# MCU_64.net
KiCad netlist of a schematic drawn in Altium Designer
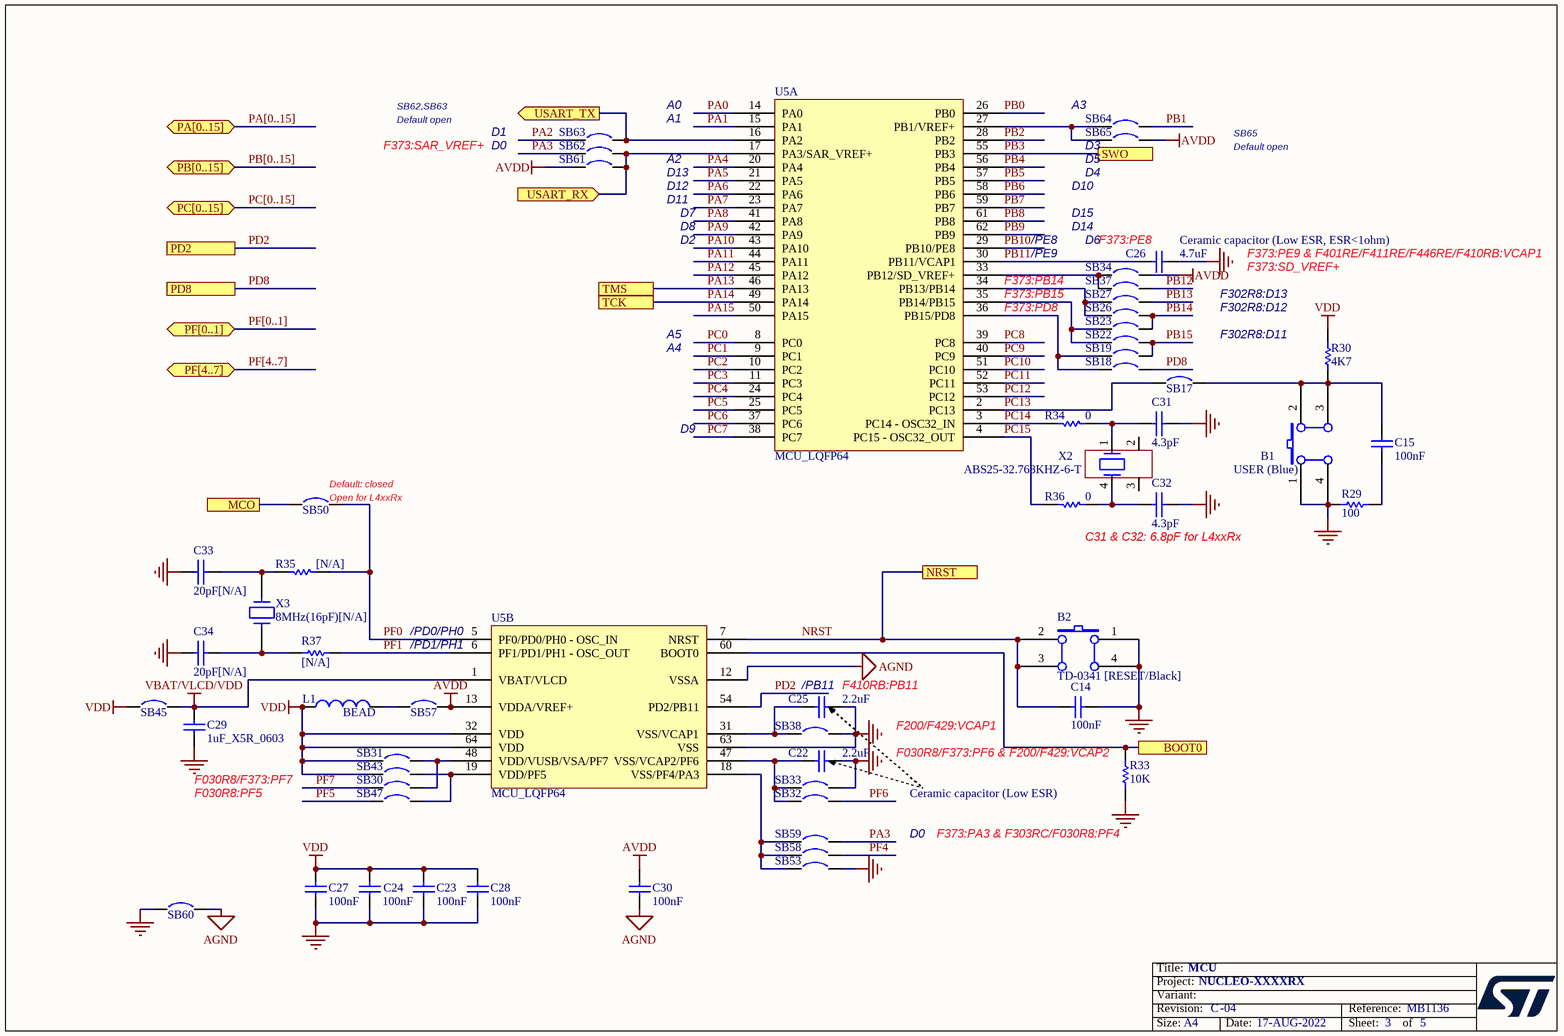
[diagram p0: MCU_64.SchDoc]

(export (version "E")
  (design (tool "Eeschema 10.0.6"))
  (components
    (comp (ref "B1")
      (value "USER (Blue)")
      (footprint "PB10")
      (description "SE PUSHBUTTON")
      (libsource (lib "Documents") (part "SW PUSHBUTTON"))
    )
    (comp (ref "B2")
      (value "TD-0341 [RESET/Black]")
      (footprint "PB10")
      (description "SE PUSHBUTTON")
      (libsource (lib "Documents") (part "SW PUSHBUTTON"))
    )
    (comp (ref "C14")
      (value "100nF")
      (footprint "0603C")
      (description "Capacitor")
      (fields (field (name "PUBLISHER") "Altium Limited"))
      (libsource (lib "Miscellaneous Devices") (part "CAP"))
    )
    (comp (ref "C15")
      (value "100nF")
      (footprint "0603C")
      (description "Capacitor")
      (fields (field (name "PUBLISHER") "Altium Limited"))
      (libsource (lib "Miscellaneous Devices") (part "CAP"))
    )
    (comp (ref "C22")
      (value "2.2uF")
      (footprint "TAN-A")
      (description "Capacitor,2.2uF,16V, X7R,10%,0805,YAGEO")
      (libsource (lib "MCD_TOOLS") (part "Cap_2.2uF_X7R_10%_0805"))
    )
    (comp (ref "C23")
      (value "100nF")
      (footprint "0603C")
      (description "Capacitor")
      (fields (field (name "PUBLISHER") "Altium Limited"))
      (libsource (lib "Miscellaneous Devices") (part "Cap"))
    )
    (comp (ref "C24")
      (value "100nF")
      (footprint "0603C")
      (description "Capacitor")
      (fields (field (name "PUBLISHER") "Altium Limited"))
      (libsource (lib "Miscellaneous Devices") (part "Cap"))
    )
    (comp (ref "C25")
      (value "2.2uF")
      (footprint "TAN-A")
      (description "Capacitor,2.2uF,16V, X7R,10%,0805,YAGEO")
      (libsource (lib "MCD_TOOLS") (part "Cap_2.2uF_X7R_10%_0805"))
    )
    (comp (ref "C26")
      (value "4.7uF")
      (footprint "TAN-A")
      (description "Capacitor,4.7uF,25V, X7R,10%,1206,YAGEO")
      (libsource (lib "MCD_TOOLS") (part "Cap_2.2uF_X7R_10%_0805"))
    )
    (comp (ref "C27")
      (value "100nF")
      (footprint "0603C")
      (description "Capacitor")
      (fields (field (name "PUBLISHER") "Altium Limited"))
      (libsource (lib "Miscellaneous Devices") (part "Cap"))
    )
    (comp (ref "C28")
      (value "100nF")
      (footprint "0603C")
      (description "Capacitor")
      (fields (field (name "PUBLISHER") "Altium Limited"))
      (libsource (lib "Miscellaneous Devices") (part "Cap"))
    )
    (comp (ref "C29")
      (value "1uF_X5R_0603")
      (footprint "0603C")
      (description "0603  X5R 1µF")
      (fields (field (name "TOLERANCE") "10%"))
      (libsource (lib "MB963_1") (part "CAP SMD 0603  X5R 1µF 25V 10%"))
    )
    (comp (ref "C30")
      (value "100nF")
      (footprint "0603C")
      (description "Capacitor")
      (fields (field (name "PUBLISHER") "Altium Limited"))
      (libsource (lib "Miscellaneous Devices") (part "Cap"))
    )
    (comp (ref "C31")
      (value "4.3pF")
      (footprint "0603C")
      (description "Capacitor")
      (libsource (lib "*") (part "CAP"))
    )
    (comp (ref "C32")
      (value "4.3pF")
      (footprint "0603C")
      (description "Capacitor")
      (libsource (lib "*") (part "CAP"))
    )
    (comp (ref "C33")
      (value "20pF[N/A]")
      (footprint "0603C")
      (description "Capacitor")
      (libsource (lib "") (part "CAP_1"))
    )
    (comp (ref "C34")
      (value "20pF[N/A]")
      (footprint "0603C")
      (description "Capacitor")
      (libsource (lib "") (part "CAP_1"))
    )
    (comp (ref "L1")
      (value "BEAD")
      (footprint "0603L")
      (description "Inductor")
      (fields (field (name "PUBLISHER") "Altium Limited"))
      (libsource (lib "Miscellaneous Devices") (part "Inductor"))
    )
    (comp (ref "R29")
      (value "100")
      (footprint "0603R")
      (description "Resistor")
      (fields (field (name "PUBLISHER") "Altium Limited"))
      (libsource (lib "Miscellaneous Devices") (part "Res1"))
    )
    (comp (ref "R30")
      (value "4K7")
      (footprint "0603R")
      (description "Resistor")
      (fields (field (name "PUBLISHER") "Altium Limited"))
      (libsource (lib "Miscellaneous Devices") (part "res1"))
    )
    (comp (ref "R33")
      (value "10K")
      (footprint "0603R")
      (description "Resistor")
      (fields (field (name "PUBLISHER") "Altium Limited"))
      (libsource (lib "Miscellaneous Devices") (part "res1"))
    )
    (comp (ref "R34")
      (value "0")
      (footprint "0603R")
      (description "Resistor")
      (fields (field (name "PUBLISHER") "Altium Limited"))
      (libsource (lib "") (part "Res1_1"))
    )
    (comp (ref "R35")
      (value "[N/A]")
      (footprint "0603R")
      (description "Resistor")
      (fields (field (name "PUBLISHER") "Altium Limited"))
      (libsource (lib "") (part "Res1_1"))
    )
    (comp (ref "R36")
      (value "0")
      (footprint "0603R")
      (description "Resistor")
      (fields (field (name "PUBLISHER") "Altium Limited"))
      (libsource (lib "") (part "Res1_1"))
    )
    (comp (ref "R37")
      (value "[N/A]")
      (footprint "0603R")
      (description "Resistor")
      (fields (field (name "PUBLISHER") "Altium Limited"))
      (libsource (lib "Miscellaneous Devices") (part "Res1"))
    )
    (comp (ref "SB17")
      (value "Circuit Breaker")
      (footprint "JP2_SMD")
      (fields (field (name "PUBLISHER") "Altium Limited"))
      (libsource (lib "MCD_TOOLS") (part "Circuit Breaker"))
    )
    (comp (ref "SB18")
      (value "Circuit Breaker")
      (footprint "JP2_SMD")
      (fields (field (name "PUBLISHER") "Altium Limited"))
      (libsource (lib "MCD_TOOLS") (part "Circuit Breaker"))
    )
    (comp (ref "SB19")
      (value "Circuit Breaker")
      (footprint "JP2_SMD")
      (fields (field (name "PUBLISHER") "Altium Limited"))
      (libsource (lib "MCD_TOOLS") (part "Circuit Breaker"))
    )
    (comp (ref "SB22")
      (value "Circuit Breaker")
      (footprint "JP2_SMD")
      (fields (field (name "PUBLISHER") "Altium Limited"))
      (libsource (lib "MCD_TOOLS") (part "Circuit Breaker"))
    )
    (comp (ref "SB23")
      (value "Circuit Breaker")
      (footprint "JP2_SMD")
      (fields (field (name "PUBLISHER") "Altium Limited"))
      (libsource (lib "MCD_TOOLS") (part "Circuit Breaker"))
    )
    (comp (ref "SB26")
      (value "Circuit Breaker")
      (footprint "JP2_SMD")
      (fields (field (name "PUBLISHER") "Altium Limited"))
      (libsource (lib "MCD_TOOLS") (part "Circuit Breaker"))
    )
    (comp (ref "SB27")
      (value "Circuit Breaker")
      (footprint "JP2_SMD")
      (fields (field (name "PUBLISHER") "Altium Limited"))
      (libsource (lib "MCD_TOOLS") (part "Circuit Breaker"))
    )
    (comp (ref "SB30")
      (value "Circuit Breaker")
      (footprint "JP2_SMD")
      (fields (field (name "PUBLISHER") "Altium Limited"))
      (libsource (lib "MCD_TOOLS") (part "Circuit Breaker"))
    )
    (comp (ref "SB31")
      (value "Circuit Breaker")
      (footprint "JP2_SMD")
      (fields (field (name "PUBLISHER") "Altium Limited"))
      (libsource (lib "MCD_TOOLS") (part "Circuit Breaker"))
    )
    (comp (ref "SB32")
      (value "Circuit Breaker")
      (footprint "JP2_SMD")
      (fields (field (name "PUBLISHER") "Altium Limited"))
      (libsource (lib "MCD_TOOLS") (part "Circuit Breaker"))
    )
    (comp (ref "SB33")
      (value "Circuit Breaker")
      (footprint "JP2_SMD")
      (fields (field (name "PUBLISHER") "Altium Limited"))
      (libsource (lib "MCD_TOOLS") (part "Circuit Breaker"))
    )
    (comp (ref "SB34")
      (value "Circuit Breaker")
      (footprint "JP2_SMD")
      (fields (field (name "PUBLISHER") "Altium Limited"))
      (libsource (lib "MCD_TOOLS") (part "Circuit Breaker"))
    )
    (comp (ref "SB37")
      (value "Circuit Breaker")
      (footprint "JP2_SMD")
      (fields (field (name "PUBLISHER") "Altium Limited"))
      (libsource (lib "MCD_TOOLS") (part "Circuit Breaker"))
    )
    (comp (ref "SB38")
      (value "Circuit Breaker")
      (footprint "JP2_SMD")
      (fields (field (name "PUBLISHER") "Altium Limited"))
      (libsource (lib "MCD_TOOLS") (part "Circuit Breaker"))
    )
    (comp (ref "SB43")
      (value "Circuit Breaker")
      (footprint "JP2_SMD")
      (fields (field (name "PUBLISHER") "Altium Limited"))
      (libsource (lib "MCD_TOOLS") (part "Circuit Breaker"))
    )
    (comp (ref "SB45")
      (value "Circuit Breaker")
      (footprint "JP2_SMD")
      (fields (field (name "PUBLISHER") "Altium Limited"))
      (libsource (lib "MCD_TOOLS") (part "Circuit Breaker"))
    )
    (comp (ref "SB47")
      (value "Circuit Breaker")
      (footprint "JP2_SMD")
      (fields (field (name "PUBLISHER") "Altium Limited"))
      (libsource (lib "MCD_TOOLS") (part "Circuit Breaker"))
    )
    (comp (ref "SB50")
      (value "Circuit Breaker")
      (footprint "JP2_SMD")
      (fields (field (name "PUBLISHER") "Altium Limited"))
      (libsource (lib "MCD_TOOLS") (part "Circuit Breaker"))
    )
    (comp (ref "SB53")
      (value "Circuit Breaker")
      (footprint "JP2_SMD")
      (fields (field (name "PUBLISHER") "Altium Limited"))
      (libsource (lib "MCD_TOOLS") (part "Circuit Breaker"))
    )
    (comp (ref "SB57")
      (value "Circuit Breaker")
      (footprint "JP2_SMD")
      (fields (field (name "PUBLISHER") "Altium Limited"))
      (libsource (lib "MCD_TOOLS") (part "Circuit Breaker"))
    )
    (comp (ref "SB58")
      (value "Circuit Breaker")
      (footprint "JP2_SMD")
      (fields (field (name "PUBLISHER") "Altium Limited"))
      (libsource (lib "MCD_TOOLS") (part "Circuit Breaker"))
    )
    (comp (ref "SB59")
      (value "Circuit Breaker")
      (footprint "JP2_SMD")
      (fields (field (name "PUBLISHER") "Altium Limited"))
      (libsource (lib "MCD_TOOLS") (part "Circuit Breaker"))
    )
    (comp (ref "SB60")
      (value "Circuit Breaker")
      (footprint "JP2_SMD")
      (fields (field (name "PUBLISHER") "Altium Limited"))
      (libsource (lib "MCD_TOOLS") (part "Circuit Breaker"))
    )
    (comp (ref "SB61")
      (value "Circuit Breaker")
      (footprint "JP2_SMD")
      (fields (field (name "PUBLISHER") "Altium Limited"))
      (libsource (lib "MCD_TOOLS") (part "Circuit Breaker"))
    )
    (comp (ref "SB62")
      (value "Circuit Breaker")
      (footprint "JP2_SMD")
      (fields (field (name "PUBLISHER") "Altium Limited"))
      (libsource (lib "MCD_TOOLS") (part "Circuit Breaker"))
    )
    (comp (ref "SB63")
      (value "Circuit Breaker")
      (footprint "JP2_SMD")
      (fields (field (name "PUBLISHER") "Altium Limited"))
      (libsource (lib "MCD_TOOLS") (part "Circuit Breaker"))
    )
    (comp (ref "SB64")
      (value "Circuit Breaker")
      (footprint "JP2_SMD")
      (fields (field (name "PUBLISHER") "Altium Limited"))
      (libsource (lib "MCD_TOOLS") (part "Circuit Breaker"))
    )
    (comp (ref "SB65")
      (value "Circuit Breaker")
      (footprint "JP2_SMD")
      (fields (field (name "PUBLISHER") "Altium Limited"))
      (libsource (lib "MCD_TOOLS") (part "Circuit Breaker"))
    )
    (comp (ref "U5") (value "MCU_LQFP64") (footprint "LQFP64") (libsource (lib "MB1136") (part "MCU_LQFP64")))
    (comp (ref "X2")
      (value "ABS25-32.768KHZ-6-T")
      (footprint "XTAL_4SM_8X3R8")
      (libsource (lib "*") (part "MC306"))
    )
    (comp (ref "X3")
      (value "8MHz(16pF)[N/A]")
      (footprint "XTAL1")
      (description "Crystal")
      (libsource (lib "*") (part "CRYSTAL"))
    )
  )
  (nets
    (net (code "1") (name "/BOOT0") (class "Default")
      (node (ref "R33") (pin "1") (pinfunction "1_1") (pintype "passive"))
      (node (ref "U5") (pin "60") (pinfunction "BOOT0_60") (pintype "passive"))
    )
    (net (code "2") (name "/MCO") (class "Default")
      (node (ref "SB50") (pin "1") (pinfunction "1_1") (pintype "passive"))
    )
    (net (code "3") (name "/NRST") (class "Default")
      (node (ref "B2") (pin "2") (pinfunction "B0_2") (pintype "passive"))
      (node (ref "B2") (pin "3") (pinfunction "B1_3") (pintype "passive"))
      (node (ref "C14") (pin "2") (pinfunction "2_2") (pintype "passive"))
      (node (ref "U5") (pin "7") (pinfunction "NRST_7") (pintype "passive"))
    )
    (net (code "4") (name "/PA0") (class "Default")
      (node (ref "U5") (pin "14") (pinfunction "PA0_14") (pintype "passive"))
    )
    (net (code "5") (name "/PA1") (class "Default")
      (node (ref "U5") (pin "15") (pinfunction "PA1_15") (pintype "passive"))
    )
    (net (code "6") (name "/PA2") (class "Default")
      (node (ref "SB63") (pin "1") (pinfunction "1_1") (pintype "passive"))
    )
    (net (code "7") (name "/PA3") (class "Default")
      (node (ref "SB59") (pin "2") (pinfunction "2_2") (pintype "passive"))
      (node (ref "SB62") (pin "1") (pinfunction "1_1") (pintype "passive"))
    )
    (net (code "8") (name "/PA4") (class "Default")
      (node (ref "U5") (pin "20") (pinfunction "PA4_20") (pintype "passive"))
    )
    (net (code "9") (name "/PA5") (class "Default")
      (node (ref "U5") (pin "21") (pinfunction "PA5_21") (pintype "passive"))
    )
    (net (code "10") (name "/PA6") (class "Default")
      (node (ref "U5") (pin "22") (pinfunction "PA6_22") (pintype "passive"))
    )
    (net (code "11") (name "/PA7") (class "Default")
      (node (ref "U5") (pin "23") (pinfunction "PA7_23") (pintype "passive"))
    )
    (net (code "12") (name "/PA8") (class "Default")
      (node (ref "U5") (pin "41") (pinfunction "PA8_41") (pintype "passive"))
    )
    (net (code "13") (name "/PA9") (class "Default")
      (node (ref "U5") (pin "42") (pinfunction "PA9_42") (pintype "passive"))
    )
    (net (code "14") (name "/PA10") (class "Default")
      (node (ref "U5") (pin "43") (pinfunction "PA10_43") (pintype "passive"))
    )
    (net (code "15") (name "/PA11") (class "Default")
      (node (ref "U5") (pin "44") (pinfunction "PA11_44") (pintype "passive"))
    )
    (net (code "16") (name "/PA12") (class "Default")
      (node (ref "U5") (pin "45") (pinfunction "PA12_45") (pintype "passive"))
    )
    (net (code "17") (name "/PA13") (class "Default")
      (node (ref "U5") (pin "46") (pinfunction "PA13_46") (pintype "passive"))
    )
    (net (code "18") (name "/PA14") (class "Default")
      (node (ref "U5") (pin "49") (pinfunction "PA14_49") (pintype "passive"))
    )
    (net (code "19") (name "/PA15") (class "Default")
      (node (ref "U5") (pin "50") (pinfunction "PA15_50") (pintype "passive"))
    )
    (net (code "21") (name "/PB0") (class "Default")
      (node (ref "U5") (pin "26") (pinfunction "PB0_26") (pintype "passive"))
    )
    (net (code "22") (name "/PB1") (class "Default")
      (node (ref "SB64") (pin "2") (pinfunction "2_2") (pintype "passive"))
    )
    (net (code "23") (name "/PB2") (class "Default")
      (node (ref "U5") (pin "28") (pinfunction "PB2_28") (pintype "passive"))
    )
    (net (code "24") (name "/PB3") (class "Default")
      (node (ref "U5") (pin "55") (pinfunction "PB3_55") (pintype "passive"))
    )
    (net (code "25") (name "/PB4") (class "Default")
      (node (ref "U5") (pin "56") (pinfunction "PB4_56") (pintype "passive"))
    )
    (net (code "26") (name "/PB5") (class "Default")
      (node (ref "U5") (pin "57") (pinfunction "PB5_57") (pintype "passive"))
    )
    (net (code "27") (name "/PB6") (class "Default")
      (node (ref "U5") (pin "58") (pinfunction "PB6_58") (pintype "passive"))
    )
    (net (code "28") (name "/PB7") (class "Default")
      (node (ref "U5") (pin "59") (pinfunction "PB7_59") (pintype "passive"))
    )
    (net (code "29") (name "/PB8") (class "Default")
      (node (ref "U5") (pin "61") (pinfunction "PB8_61") (pintype "passive"))
    )
    (net (code "30") (name "/PB9") (class "Default")
      (node (ref "U5") (pin "62") (pinfunction "PB9_62") (pintype "passive"))
    )
    (net (code "31") (name "/PB10") (class "Default")
      (node (ref "U5") (pin "29") (pinfunction "PB10/PE8_29") (pintype "passive"))
    )
    (net (code "32") (name "/PB11") (class "Default")
      (node (ref "C26") (pin "1") (pinfunction "1_1") (pintype "passive"))
      (node (ref "U5") (pin "30") (pinfunction "PB11/VCAP1_30") (pintype "passive"))
    )
    (net (code "33") (name "/PB12") (class "Default")
      (node (ref "SB37") (pin "2") (pinfunction "2_2") (pintype "passive"))
    )
    (net (code "34") (name "/PB13") (class "Default")
      (node (ref "SB27") (pin "2") (pinfunction "2_2") (pintype "passive"))
    )
    (net (code "35") (name "/PB14") (class "Default")
      (node (ref "SB23") (pin "2") (pinfunction "2_2") (pintype "passive"))
      (node (ref "SB26") (pin "2") (pinfunction "2_2") (pintype "passive"))
    )
    (net (code "36") (name "/PB15") (class "Default")
      (node (ref "SB19") (pin "2") (pinfunction "2_2") (pintype "passive"))
      (node (ref "SB22") (pin "2") (pinfunction "2_2") (pintype "passive"))
    )
    (net (code "38") (name "/PC0") (class "Default")
      (node (ref "U5") (pin "8") (pinfunction "PC0_8") (pintype "passive"))
    )
    (net (code "39") (name "/PC1") (class "Default")
      (node (ref "U5") (pin "9") (pinfunction "PC1_9") (pintype "passive"))
    )
    (net (code "40") (name "/PC2") (class "Default")
      (node (ref "U5") (pin "10") (pinfunction "PC2_10") (pintype "passive"))
    )
    (net (code "41") (name "/PC3") (class "Default")
      (node (ref "U5") (pin "11") (pinfunction "PC3_11") (pintype "passive"))
    )
    (net (code "42") (name "/PC4") (class "Default")
      (node (ref "U5") (pin "24") (pinfunction "PC4_24") (pintype "passive"))
    )
    (net (code "43") (name "/PC5") (class "Default")
      (node (ref "U5") (pin "25") (pinfunction "PC5_25") (pintype "passive"))
    )
    (net (code "44") (name "/PC6") (class "Default")
      (node (ref "U5") (pin "37") (pinfunction "PC6_37") (pintype "passive"))
    )
    (net (code "45") (name "/PC7") (class "Default")
      (node (ref "U5") (pin "38") (pinfunction "PC7_38") (pintype "passive"))
    )
    (net (code "46") (name "/PC8") (class "Default")
      (node (ref "U5") (pin "39") (pinfunction "PC8_39") (pintype "passive"))
    )
    (net (code "47") (name "/PC9") (class "Default")
      (node (ref "U5") (pin "40") (pinfunction "PC9_40") (pintype "passive"))
    )
    (net (code "48") (name "/PC10") (class "Default")
      (node (ref "U5") (pin "51") (pinfunction "PC10_51") (pintype "passive"))
    )
    (net (code "49") (name "/PC11") (class "Default")
      (node (ref "U5") (pin "52") (pinfunction "PC11_52") (pintype "passive"))
    )
    (net (code "50") (name "/PC12") (class "Default")
      (node (ref "U5") (pin "53") (pinfunction "PC12_53") (pintype "passive"))
    )
    (net (code "51") (name "/PC13") (class "Default")
      (node (ref "SB17") (pin "1") (pinfunction "1_1") (pintype "passive"))
      (node (ref "U5") (pin "2") (pinfunction "PC13_2") (pintype "passive"))
    )
    (net (code "52") (name "/PC14") (class "Default")
      (node (ref "R34") (pin "2") (pinfunction "2_2") (pintype "passive"))
      (node (ref "U5") (pin "3") (pinfunction "PC14_-_OSC32_IN_3") (pintype "passive"))
    )
    (net (code "53") (name "/PC15") (class "Default")
      (node (ref "R36") (pin "2") (pinfunction "2_2") (pintype "passive"))
      (node (ref "U5") (pin "4") (pinfunction "PC15_-_OSC32_OUT_4") (pintype "passive"))
    )
    (net (code "55") (name "/PD2") (class "Default")
      (node (ref "U5") (pin "54") (pinfunction "PD2/PB11_54") (pintype "passive"))
    )
    (net (code "56") (name "/PD8") (class "Default")
      (node (ref "SB18") (pin "2") (pinfunction "2_2") (pintype "passive"))
    )
    (net (code "57") (name "/PF0") (class "Default")
      (node (ref "R35") (pin "1") (pinfunction "1_1") (pintype "passive"))
      (node (ref "SB50") (pin "2") (pinfunction "2_2") (pintype "passive"))
      (node (ref "U5") (pin "5") (pinfunction "PF0/PD0/PH0_-_OSC_IN_5") (pintype "passive"))
    )
    (net (code "58") (name "/PF1") (class "Default")
      (node (ref "R37") (pin "1") (pinfunction "1_1") (pintype "passive"))
      (node (ref "U5") (pin "6") (pinfunction "PF1/PD1/PH1_-_OSC_OUT_6") (pintype "passive"))
    )
    (net (code "59") (name "/PF4") (class "Default")
      (node (ref "SB58") (pin "2") (pinfunction "2_2") (pintype "passive"))
    )
    (net (code "60") (name "/PF5") (class "Default")
      (node (ref "SB47") (pin "1") (pinfunction "1_1") (pintype "passive"))
    )
    (net (code "61") (name "/PF6") (class "Default")
      (node (ref "SB32") (pin "2") (pinfunction "2_2") (pintype "passive"))
    )
    (net (code "62") (name "/PF7") (class "Default")
      (node (ref "SB30") (pin "1") (pinfunction "1_1") (pintype "passive"))
    )
    (net (code "65") (name "/USART_RX") (class "Default")
      (node (ref "SB61") (pin "2") (pinfunction "2_2") (pintype "passive"))
      (node (ref "SB62") (pin "2") (pinfunction "2_2") (pintype "passive"))
      (node (ref "U5") (pin "17") (pinfunction "PA3/SAR_VREF+_17") (pintype "passive"))
    )
    (net (code "66") (name "/USART_TX") (class "Default")
      (node (ref "SB63") (pin "2") (pinfunction "2_2") (pintype "passive"))
      (node (ref "U5") (pin "16") (pinfunction "PA2_16") (pintype "passive"))
    )
    (net (code "67") (name "AGND") (class "Default")
      (node (ref "C30") (pin "2") (pinfunction "2_2") (pintype "passive"))
      (node (ref "SB60") (pin "2") (pinfunction "2_2") (pintype "passive"))
      (node (ref "U5") (pin "12") (pinfunction "VSSA_12") (pintype "passive"))
    )
    (net (code "68") (name "AVDD") (class "Default")
      (node (ref "C30") (pin "1") (pinfunction "1_1") (pintype "passive"))
      (node (ref "SB34") (pin "2") (pinfunction "2_2") (pintype "passive"))
      (node (ref "SB57") (pin "2") (pinfunction "2_2") (pintype "passive"))
      (node (ref "SB61") (pin "1") (pinfunction "1_1") (pintype "passive"))
      (node (ref "SB65") (pin "2") (pinfunction "2_2") (pintype "passive"))
      (node (ref "U5") (pin "13") (pinfunction "VDDA/VREF+_13") (pintype "passive"))
    )
    (net (code "69") (name "GND") (class "Default")
      (node (ref "B1") (pin "1") (pinfunction "A0_1") (pintype "passive"))
      (node (ref "B1") (pin "4") (pinfunction "A1_4") (pintype "passive"))
      (node (ref "B2") (pin "1") (pinfunction "A0_1") (pintype "passive"))
      (node (ref "B2") (pin "4") (pinfunction "A1_4") (pintype "passive"))
      (node (ref "C14") (pin "1") (pinfunction "1_1") (pintype "passive"))
      (node (ref "C22") (pin "2") (pinfunction "2_2") (pintype "passive"))
      (node (ref "C23") (pin "2") (pinfunction "2_2") (pintype "passive"))
      (node (ref "C24") (pin "2") (pinfunction "2_2") (pintype "passive"))
      (node (ref "C25") (pin "2") (pinfunction "2_2") (pintype "passive"))
      (node (ref "C26") (pin "2") (pinfunction "2_2") (pintype "passive"))
      (node (ref "C27") (pin "2") (pinfunction "2_2") (pintype "passive"))
      (node (ref "C28") (pin "2") (pinfunction "2_2") (pintype "passive"))
      (node (ref "C29") (pin "2") (pinfunction "2_2") (pintype "passive"))
      (node (ref "C31") (pin "2") (pinfunction "2_2") (pintype "passive"))
      (node (ref "C32") (pin "2") (pinfunction "2_2") (pintype "passive"))
      (node (ref "C33") (pin "2") (pinfunction "2_2") (pintype "passive"))
      (node (ref "C34") (pin "2") (pinfunction "2_2") (pintype "passive"))
      (node (ref "R29") (pin "1") (pinfunction "1_1") (pintype "passive"))
      (node (ref "R33") (pin "2") (pinfunction "2_2") (pintype "passive"))
      (node (ref "SB33") (pin "2") (pinfunction "2_2") (pintype "passive"))
      (node (ref "SB38") (pin "2") (pinfunction "2_2") (pintype "passive"))
      (node (ref "SB53") (pin "2") (pinfunction "2_2") (pintype "passive"))
      (node (ref "SB60") (pin "1") (pinfunction "1_1") (pintype "passive"))
      (node (ref "U5") (pin "63") (pinfunction "VSS_63") (pintype "passive"))
    )
    (net (code "70") (name "Net-(B1-B0)") (class "Default")
      (node (ref "B1") (pin "2") (pinfunction "B0_2") (pintype "passive"))
      (node (ref "B1") (pin "3") (pinfunction "B1_3") (pintype "passive"))
      (node (ref "C15") (pin "2") (pinfunction "2_2") (pintype "passive"))
      (node (ref "R30") (pin "1") (pinfunction "1_1") (pintype "passive"))
      (node (ref "SB17") (pin "2") (pinfunction "2_2") (pintype "passive"))
    )
    (net (code "71") (name "Net-(C15-Pad1)") (class "Default")
      (node (ref "C15") (pin "1") (pinfunction "1_1") (pintype "passive"))
      (node (ref "R29") (pin "2") (pinfunction "2_2") (pintype "passive"))
    )
    (net (code "72") (name "Net-(C31-Pad1)") (class "Default")
      (node (ref "C31") (pin "1") (pinfunction "1_1") (pintype "passive"))
      (node (ref "R34") (pin "1") (pinfunction "1_1") (pintype "passive"))
      (node (ref "X2") (pin "1") (pinfunction "1_1") (pintype "passive"))
    )
    (net (code "73") (name "Net-(C32-Pad1)") (class "Default")
      (node (ref "C32") (pin "1") (pinfunction "1_1") (pintype "passive"))
      (node (ref "R36") (pin "1") (pinfunction "1_1") (pintype "passive"))
      (node (ref "X2") (pin "4") (pinfunction "4_4") (pintype "passive"))
    )
    (net (code "74") (name "Net-(C33-Pad1)") (class "Default")
      (node (ref "C33") (pin "1") (pinfunction "1_1") (pintype "passive"))
      (node (ref "R35") (pin "2") (pinfunction "2_2") (pintype "passive"))
      (node (ref "X3") (pin "2") (pinfunction "2_2") (pintype "passive"))
    )
    (net (code "75") (name "Net-(C34-Pad1)") (class "Default")
      (node (ref "C34") (pin "1") (pinfunction "1_1") (pintype "passive"))
      (node (ref "R37") (pin "2") (pinfunction "2_2") (pintype "passive"))
      (node (ref "X3") (pin "1") (pinfunction "1_1") (pintype "passive"))
    )
    (net (code "76") (name "Net-(L1-Pad2)") (class "Default")
      (node (ref "L1") (pin "2") (pinfunction "2_2") (pintype "passive"))
      (node (ref "SB57") (pin "1") (pinfunction "1_1") (pintype "passive"))
    )
    (net (code "77") (name "Net-(U5A-PB1{slash}VREF+)") (class "Default")
      (node (ref "SB64") (pin "1") (pinfunction "1_1") (pintype "passive"))
      (node (ref "SB65") (pin "1") (pinfunction "1_1") (pintype "passive"))
      (node (ref "U5") (pin "27") (pinfunction "PB1/VREF+_27") (pintype "passive"))
    )
    (net (code "78") (name "Net-(U5A-PB12{slash}SD_VREF+)") (class "Default")
      (node (ref "SB34") (pin "1") (pinfunction "1_1") (pintype "passive"))
      (node (ref "SB37") (pin "1") (pinfunction "1_1") (pintype "passive"))
      (node (ref "U5") (pin "33") (pinfunction "PB12/SD_VREF+_33") (pintype "passive"))
    )
    (net (code "79") (name "Net-(U5A-PB13{slash}PB14)") (class "Default")
      (node (ref "SB26") (pin "1") (pinfunction "1_1") (pintype "passive"))
      (node (ref "SB27") (pin "1") (pinfunction "1_1") (pintype "passive"))
      (node (ref "U5") (pin "34") (pinfunction "PB13/PB14_34") (pintype "passive"))
    )
    (net (code "80") (name "Net-(U5A-PB14{slash}PB15)") (class "Default")
      (node (ref "SB22") (pin "1") (pinfunction "1_1") (pintype "passive"))
      (node (ref "SB23") (pin "1") (pinfunction "1_1") (pintype "passive"))
      (node (ref "U5") (pin "35") (pinfunction "PB14/PB15_35") (pintype "passive"))
    )
    (net (code "81") (name "Net-(U5A-PB15{slash}PD8)") (class "Default")
      (node (ref "SB18") (pin "1") (pinfunction "1_1") (pintype "passive"))
      (node (ref "SB19") (pin "1") (pinfunction "1_1") (pintype "passive"))
      (node (ref "U5") (pin "36") (pinfunction "PB15/PD8_36") (pintype "passive"))
    )
    (net (code "82") (name "Net-(U5B-VDD{slash}PF5)") (class "Default")
      (node (ref "SB43") (pin "2") (pinfunction "2_2") (pintype "passive"))
      (node (ref "SB47") (pin "2") (pinfunction "2_2") (pintype "passive"))
      (node (ref "U5") (pin "19") (pinfunction "VDD/PF5_19") (pintype "passive"))
    )
    (net (code "83") (name "Net-(U5B-VDD{slash}VUSB{slash}VSA{slash}PF7)") (class "Default")
      (node (ref "SB30") (pin "2") (pinfunction "2_2") (pintype "passive"))
      (node (ref "SB31") (pin "2") (pinfunction "2_2") (pintype "passive"))
      (node (ref "U5") (pin "48") (pinfunction "VDD/VUSB/VSA/PF7_48") (pintype "passive"))
    )
    (net (code "84") (name "Net-(U5B-VSS{slash}PF4{slash}PA3)") (class "Default")
      (node (ref "SB53") (pin "1") (pinfunction "1_1") (pintype "passive"))
      (node (ref "SB58") (pin "1") (pinfunction "1_1") (pintype "passive"))
      (node (ref "SB59") (pin "1") (pinfunction "1_1") (pintype "passive"))
      (node (ref "U5") (pin "18") (pinfunction "VSS/PF4/PA3_18") (pintype "passive"))
    )
    (net (code "85") (name "Net-(U5B-VSS{slash}VCAP1)") (class "Default")
      (node (ref "C25") (pin "1") (pinfunction "1_1") (pintype "passive"))
      (node (ref "SB38") (pin "1") (pinfunction "1_1") (pintype "passive"))
      (node (ref "U5") (pin "31") (pinfunction "VSS/VCAP1_31") (pintype "passive"))
    )
    (net (code "86") (name "Net-(U5B-VSS{slash}VCAP2{slash}PF6)") (class "Default")
      (node (ref "C22") (pin "1") (pinfunction "1_1") (pintype "passive"))
      (node (ref "SB32") (pin "1") (pinfunction "1_1") (pintype "passive"))
      (node (ref "SB33") (pin "1") (pinfunction "1_1") (pintype "passive"))
      (node (ref "U5") (pin "47") (pinfunction "VSS/VCAP2/PF6_47") (pintype "passive"))
    )
    (net (code "87") (name "VBAT{slash}VLCD{slash}VDD") (class "Default")
      (node (ref "C29") (pin "1") (pinfunction "1_1") (pintype "passive"))
      (node (ref "SB45") (pin "2") (pinfunction "2_2") (pintype "passive"))
      (node (ref "U5") (pin "1") (pinfunction "VBAT/VLCD_1") (pintype "passive"))
    )
    (net (code "88") (name "VDD") (class "Default")
      (node (ref "C23") (pin "1") (pinfunction "1_1") (pintype "passive"))
      (node (ref "C24") (pin "1") (pinfunction "1_1") (pintype "passive"))
      (node (ref "C27") (pin "1") (pinfunction "1_1") (pintype "passive"))
      (node (ref "C28") (pin "1") (pinfunction "1_1") (pintype "passive"))
      (node (ref "L1") (pin "1") (pinfunction "1_1") (pintype "passive"))
      (node (ref "R30") (pin "2") (pinfunction "2_2") (pintype "passive"))
      (node (ref "SB31") (pin "1") (pinfunction "1_1") (pintype "passive"))
      (node (ref "SB43") (pin "1") (pinfunction "1_1") (pintype "passive"))
      (node (ref "SB45") (pin "1") (pinfunction "1_1") (pintype "passive"))
      (node (ref "U5") (pin "32") (pinfunction "VDD_32") (pintype "passive"))
      (node (ref "U5") (pin "64") (pinfunction "VDD_64") (pintype "passive"))
    )
    (net (code "89") (name "unconnected-(X2-Pad2)") (class "Default")
      (node (ref "X2") (pin "2") (pinfunction "2_2") (pintype "passive"))
    )
    (net (code "90") (name "unconnected-(X2-Pad3)") (class "Default")
      (node (ref "X2") (pin "3") (pinfunction "3_3") (pintype "passive"))
    )
  )
)
